# Power_Distribution_-_Rear_camera_and_Spa.net
KiCad netlist of a schematic drawn in Altium Designer
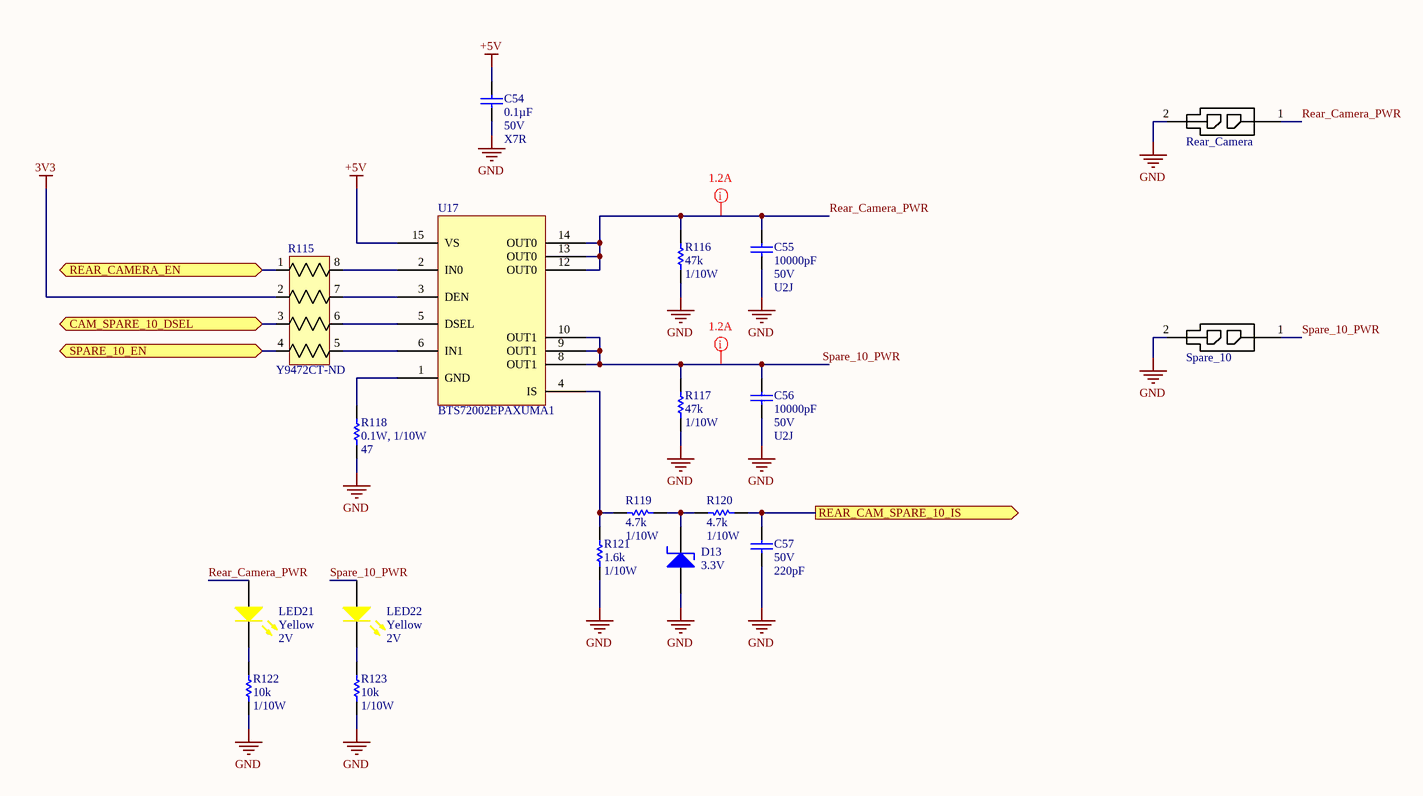
[diagram p0: Power Distribution - Rear camera and Spare 10.SchDoc]

(export (version "E")
  (design (tool "Eeschema 10.0.6"))
  (components
    (comp (ref "C54")
      (value "CAP CER 0.1UF 50V 10% X7R 0603")
      (footprint "CAP, 0603")
      (description "0.10µF ±10% 50V Ceramic Capacitor X7R 0603 (1608 Metric)")
      (fields
        (field (name "TOLERANCE") "±10%")
        (field (name "CAPACITANCE") "0.1µF")
        (field (name "VOLTAGE") "50V")
        (field (name "TEMPERATURE COEFFICIENT") "X7R")
      )
      (libsource (lib "Schematic Diagrams") (part "CAP CER 0.1UF 50V 10% X7R 0603"))
    )
    (comp (ref "C55")
      (value "CAP CER 10nF 50V 5% X7R 0603")
      (footprint "CAP, 0603")
      (description "10000pF ±5% 50V Ceramic Capacitor U2J 0603 (1608 Metric)")
      (fields
        (field (name "TOLERANCE") "±5%")
        (field (name "CAPACITANCE") "10000pF")
        (field (name "VOLTAGE") "50V")
        (field (name "TEMPERATURE COEFFICIENT") "U2J")
      )
      (libsource (lib "Schematic Diagrams") (part "CAP CER 10nF 50V 5% X7R 0603"))
    )
    (comp (ref "C56")
      (value "CAP CER 10nF 50V 5% X7R 0603")
      (footprint "CAP, 0603")
      (description "10000pF ±5% 50V Ceramic Capacitor U2J 0603 (1608 Metric)")
      (fields
        (field (name "TOLERANCE") "±5%")
        (field (name "CAPACITANCE") "10000pF")
        (field (name "VOLTAGE") "50V")
        (field (name "TEMPERATURE COEFFICIENT") "U2J")
      )
      (libsource (lib "Schematic Diagrams") (part "CAP CER 10nF 50V 5% X7R 0603"))
    )
    (comp (ref "C57")
      (value "CAP CER 220PF 50V C0G/NP0 0603")
      (footprint "CAP, 0603")
      (description "220pF ±5% 50V Ceramic Capacitor C0G, NP0 0603 (1608 Metric)")
      (fields
        (field (name "MANUFACTURER") "KEMET")
        (field (name "TOLERANCE") "5%")
        (field (name "VOLTAGE RATING") "50V")
        (field (name "CAPACITANCE") "220pF")
      )
      (libsource (lib "Schematic Diagrams") (part "CAP CER 220PF 50V C0G/NP0 0603"))
    )
    (comp (ref "D13")
      (value "DIODE ZENER 3.3V 200MW SOD323")
      (footprint "sod-323")
      (description "Zener Diode 3.3V 200mW ±5% Surface Mount SOD-323")
      (fields (field (name "VOLTAGE") "3.3V"))
      (libsource (lib "Schematic Diagrams") (part "DIODE ZENER 3.3V 200MW SOD323"))
    )
    (comp (ref "LED21")
      (value "LED YELLOW CLEAR 2.1V 0603")
      (footprint "LED_0603")
      (description "Yellow 590nm LED Indication - Discrete 2V 0603 (1608 Metric)")
      (fields
        (field (name "MANUFACTURER") "Wurth Electronics Inc.")
        (field (name "MANUFACTURER PART NUMBER") "150060YS75000")
        (field (name "COLOR") "Yellow")
        (field (name "VOLTAGE - FORWARD (VF) (TYP)") "2V")
      )
      (libsource (lib "Schematic Diagrams") (part "LED YELLOW CLEAR 2.1V 0603"))
    )
    (comp (ref "LED22")
      (value "LED YELLOW CLEAR 2.1V 0603")
      (footprint "LED_0603")
      (description "Yellow 590nm LED Indication - Discrete 2V 0603 (1608 Metric)")
      (fields
        (field (name "MANUFACTURER") "Wurth Electronics Inc.")
        (field (name "MANUFACTURER PART NUMBER") "150060YS75000")
        (field (name "COLOR") "Yellow")
        (field (name "VOLTAGE - FORWARD (VF) (TYP)") "2V")
      )
      (libsource (lib "Schematic Diagrams") (part "LED YELLOW CLEAR 2.1V 0603"))
    )
    (comp (ref "R115")
      (value "RES ARRAY 4 RES 4.7K OHM 1206")
      (footprint "RES ARRAY 4RES 1206")
      (fields (field (name "TOLERANCE") "±5%") (field (name "SUPPLIER PART NUMBER 1") "Y9472CT-ND"))
      (libsource (lib "Schematic Diagrams") (part "RES ARRAY 4 RES 4.7K OHM 1206"))
    )
    (comp (ref "R116")
      (value "RES 47K OHM 1% 1/10W 0603")
      (footprint "RES, 0603")
      (description "47 kOhms ±1% 0.1W, 1/10W Chip Resistor 0603 (1608 Metric) Automotive AEC-Q200 Thick Film")
      (fields
        (field (name "MANUFACTURER") "Panasonic")
        (field (name "MANUFACTURER PART NUMBER") "ERJ3EKF4702V")
        (field (name "RESISTANCE") "47k")
        (field (name "POWER RATING") "1/10W")
      )
      (libsource (lib "Schematic Diagrams") (part "RES 47K OHM 1% 1/10W 0603"))
    )
    (comp (ref "R117")
      (value "RES 47K OHM 1% 1/10W 0603")
      (footprint "RES, 0603")
      (description "47 kOhms ±1% 0.1W, 1/10W Chip Resistor 0603 (1608 Metric) Automotive AEC-Q200 Thick Film")
      (fields
        (field (name "MANUFACTURER") "Panasonic")
        (field (name "MANUFACTURER PART NUMBER") "ERJ3EKF4702V")
        (field (name "RESISTANCE") "47k")
        (field (name "POWER RATING") "1/10W")
      )
      (libsource (lib "Schematic Diagrams") (part "RES 47K OHM 1% 1/10W 0603"))
    )
    (comp (ref "R118")
      (value "RES SMD 47 OHM 1% 1/10W 0603")
      (footprint "RES, 0603")
      (fields
        (field (name "TOLERANCE") "±1%")
        (field (name "POWER (WATTS)") "0.1W, 1/10W")
        (field (name "VALUES") "47")
      )
      (libsource (lib "Schematic Diagrams") (part "RES SMD 47 OHM 1% 1/10W 0603"))
    )
    (comp (ref "R119")
      (value "RES 4.7K OHM 1% 1/10W 0603")
      (footprint "RES, 0603")
      (description "4.7k Ohm ±1% 0.1W, 1/10W Chip Resistor 0603 (1608 Metric) Moisture Resistant Thick Film")
      (fields
        (field (name "TOLERANCE") "±1%")
        (field (name "RESISTANCE (OHMS)") "4.7k")
        (field (name "POWER (WATTS)") "1/10W")
      )
      (libsource (lib "Schematic Diagrams") (part "RES 4.7K OHM 1% 1/10W 0603"))
    )
    (comp (ref "R120")
      (value "RES 4.7K OHM 1% 1/10W 0603")
      (footprint "RES, 0603")
      (description "4.7k Ohm ±1% 0.1W, 1/10W Chip Resistor 0603 (1608 Metric) Moisture Resistant Thick Film")
      (fields
        (field (name "TOLERANCE") "±1%")
        (field (name "RESISTANCE (OHMS)") "4.7k")
        (field (name "POWER (WATTS)") "1/10W")
      )
      (libsource (lib "Schematic Diagrams") (part "RES 4.7K OHM 1% 1/10W 0603"))
    )
    (comp (ref "R121")
      (value "RES 1.6K OHM 1% 1/10W 0603")
      (footprint "RES, 0603")
      (description "1.6 kOhms ±1% 0.1W, 1/10W Chip Resistor 0603 (1608 Metric) Moisture Resistant Thick Film")
      (fields
        (field (name "MANUFACTURER") "Yageo")
        (field (name "MANUFACTURER PART NUMBER") "RC0603FR-071K6L")
        (field (name "RESISTANCE") "1.6k")
        (field (name "POWER RATING") "1/10W")
      )
      (libsource (lib "Schematic Diagrams") (part "RES 1.6K OHM 1% 1/10W 0603"))
    )
    (comp (ref "R122")
      (value "RES 10K OHM 1% 1/10W 0603")
      (footprint "RES, 0603")
      (description "RES SMD 10K OHM 1% 1/10W 0603")
      (fields
        (field (name "TOLERANCE") "±1%")
        (field (name "RESISTANCE") "10k")
        (field (name "POWER") "1/10W")
      )
      (libsource (lib "Schematic Diagrams") (part "RES 10K OHM 1% 1/10W 0603"))
    )
    (comp (ref "R123")
      (value "RES 10K OHM 1% 1/10W 0603")
      (footprint "RES, 0603")
      (description "RES SMD 10K OHM 1% 1/10W 0603")
      (fields
        (field (name "TOLERANCE") "±1%")
        (field (name "RESISTANCE") "10k")
        (field (name "POWER") "1/10W")
      )
      (libsource (lib "Schematic Diagrams") (part "RES 10K OHM 1% 1/10W 0603"))
    )
    (comp (ref "Rear_Camera")
      (value "CONN 2POS MICRO-FIT 3mm")
      (footprint "CONN, 2POS MICRO-FIT")
      (description "Connector Header Through Hole 2 position")
      (fields (field (name "MANUFACTURER") "Molex") (field (name "MANUFACTURER PART NUMBER") "43045-0227"))
      (libsource (lib "Schematic Diagrams") (part "CONN 2POS MICRO-FIT 3mm"))
    )
    (comp (ref "Spare_10")
      (value "CONN 2POS MICRO-FIT 3mm")
      (footprint "CONN, 2POS MICRO-FIT")
      (description "Connector Header Through Hole 2 position")
      (fields (field (name "MANUFACTURER") "Molex") (field (name "MANUFACTURER PART NUMBER") "43045-0227"))
      (libsource (lib "Schematic Diagrams") (part "CONN 2POS MICRO-FIT 3mm"))
    )
    (comp (ref "U17")
      (value "IC LOAD SWITCH BTS7200-2EPA PG-TSDSO-14_1")
      (footprint "IC LOAD SWITCH PG-TSDSO-14-22")
      (description "Power Switch/Driver 1:1 N-Channel 1.2A PG-TSDSO-14-22")
      (fields
        (field (name "MANUFACTURER") "Infineon")
        (field (name "MANUFACTURER PART NUMBER") "BTS72002EPAXUMA1")
      )
      (libsource (lib "Schematic Diagrams") (part "IC LOAD SWITCH BTS7200-2EPA PG-TSDSO-14_1"))
    )
  )
  (nets
    (net (code "1") (name "+5V") (class "Default")
      (node (ref "C54") (pin "1") (pinfunction "1_1") (pintype "passive"))
      (node (ref "U17") (pin "15") (pinfunction "VS_15") (pintype "passive"))
    )
    (net (code "2") (name "/CAM_SPARE_10_DSEL") (class "Default")
      (node (ref "R115") (pin "3") (pinfunction "3_3") (pintype "passive"))
    )
    (net (code "3") (name "/REAR_CAMERA_EN") (class "Default")
      (node (ref "R115") (pin "1") (pinfunction "1_1") (pintype "passive"))
    )
    (net (code "4") (name "/REAR_CAM_SPARE_10_IS") (class "Default")
      (node (ref "C57") (pin "1") (pinfunction "1_1") (pintype "passive"))
      (node (ref "R120") (pin "1") (pinfunction "1_1") (pintype "passive"))
    )
    (net (code "5") (name "/Rear_Camera_PWR") (class "Default")
      (node (ref "C55") (pin "1") (pinfunction "1_1") (pintype "passive"))
      (node (ref "LED21") (pin "1") (pinfunction "A_1") (pintype "passive"))
      (node (ref "R116") (pin "1") (pinfunction "1_1") (pintype "passive"))
      (node (ref "Rear_Camera") (pin "1") (pinfunction "1_1") (pintype "passive"))
      (node (ref "U17") (pin "12") (pinfunction "OUT0_12") (pintype "passive"))
      (node (ref "U17") (pin "13") (pinfunction "OUT0_13") (pintype "passive"))
      (node (ref "U17") (pin "14") (pinfunction "OUT0_14") (pintype "passive"))
    )
    (net (code "6") (name "/SPARE_10_EN") (class "Default")
      (node (ref "R115") (pin "4") (pinfunction "4_4") (pintype "passive"))
    )
    (net (code "7") (name "/Spare_10_PWR") (class "Default")
      (node (ref "C56") (pin "1") (pinfunction "1_1") (pintype "passive"))
      (node (ref "LED22") (pin "1") (pinfunction "A_1") (pintype "passive"))
      (node (ref "R117") (pin "1") (pinfunction "1_1") (pintype "passive"))
      (node (ref "Spare_10") (pin "1") (pinfunction "1_1") (pintype "passive"))
      (node (ref "U17") (pin "10") (pinfunction "OUT1_10") (pintype "passive"))
      (node (ref "U17") (pin "8") (pinfunction "OUT1_8") (pintype "passive"))
      (node (ref "U17") (pin "9") (pinfunction "OUT1_9") (pintype "passive"))
    )
    (net (code "8") (name "3V3") (class "Default")
      (node (ref "R115") (pin "2") (pinfunction "2_2") (pintype "passive"))
    )
    (net (code "9") (name "GND") (class "Default")
      (node (ref "C54") (pin "2") (pinfunction "2_2") (pintype "passive"))
      (node (ref "C55") (pin "2") (pinfunction "2_2") (pintype "passive"))
      (node (ref "C56") (pin "2") (pinfunction "2_2") (pintype "passive"))
      (node (ref "C57") (pin "2") (pinfunction "2_2") (pintype "passive"))
      (node (ref "D13") (pin "1") (pinfunction "A_1") (pintype "passive"))
      (node (ref "R116") (pin "2") (pinfunction "2_2") (pintype "passive"))
      (node (ref "R117") (pin "2") (pinfunction "2_2") (pintype "passive"))
      (node (ref "R118") (pin "2") (pinfunction "2_2") (pintype "passive"))
      (node (ref "R121") (pin "2") (pinfunction "2_2") (pintype "passive"))
      (node (ref "R122") (pin "2") (pinfunction "2_2") (pintype "passive"))
      (node (ref "R123") (pin "2") (pinfunction "2_2") (pintype "passive"))
      (node (ref "Rear_Camera") (pin "2") (pinfunction "2_2") (pintype "passive"))
      (node (ref "Spare_10") (pin "2") (pinfunction "2_2") (pintype "passive"))
    )
    (net (code "10") (name "Net-(D13-K)") (class "Default")
      (node (ref "D13") (pin "2") (pinfunction "K_2") (pintype "passive"))
      (node (ref "R119") (pin "1") (pinfunction "1_1") (pintype "passive"))
      (node (ref "R120") (pin "2") (pinfunction "2_2") (pintype "passive"))
    )
    (net (code "11") (name "Net-(LED21-K)") (class "Default")
      (node (ref "LED21") (pin "2") (pinfunction "K_2") (pintype "passive"))
      (node (ref "R122") (pin "1") (pinfunction "1_1") (pintype "passive"))
    )
    (net (code "12") (name "Net-(LED22-K)") (class "Default")
      (node (ref "LED22") (pin "2") (pinfunction "K_2") (pintype "passive"))
      (node (ref "R123") (pin "1") (pinfunction "1_1") (pintype "passive"))
    )
    (net (code "13") (name "Net-(U17-DEN)") (class "Default")
      (node (ref "R115") (pin "7") (pinfunction "7_7") (pintype "passive"))
      (node (ref "U17") (pin "3") (pinfunction "DEN_3") (pintype "passive"))
    )
    (net (code "14") (name "Net-(U17-DSEL)") (class "Default")
      (node (ref "R115") (pin "6") (pinfunction "6_6") (pintype "passive"))
      (node (ref "U17") (pin "5") (pinfunction "DSEL_5") (pintype "passive"))
    )
    (net (code "15") (name "Net-(U17-GND)") (class "Default")
      (node (ref "R118") (pin "1") (pinfunction "1_1") (pintype "passive"))
      (node (ref "U17") (pin "1") (pinfunction "GND_1") (pintype "passive"))
    )
    (net (code "16") (name "Net-(U17-IN0)") (class "Default")
      (node (ref "R115") (pin "8") (pinfunction "8_8") (pintype "passive"))
      (node (ref "U17") (pin "2") (pinfunction "IN0_2") (pintype "passive"))
    )
    (net (code "17") (name "Net-(U17-IN1)") (class "Default")
      (node (ref "R115") (pin "5") (pinfunction "5_5") (pintype "passive"))
      (node (ref "U17") (pin "6") (pinfunction "IN1_6") (pintype "passive"))
    )
    (net (code "18") (name "Net-(U17-IS)") (class "Default")
      (node (ref "R119") (pin "2") (pinfunction "2_2") (pintype "passive"))
      (node (ref "R121") (pin "1") (pinfunction "1_1") (pintype "passive"))
      (node (ref "U17") (pin "4") (pinfunction "IS_4") (pintype "passive"))
    )
  )
)
